# my.net
KiCad netlist of a schematic drawn in EAGLE
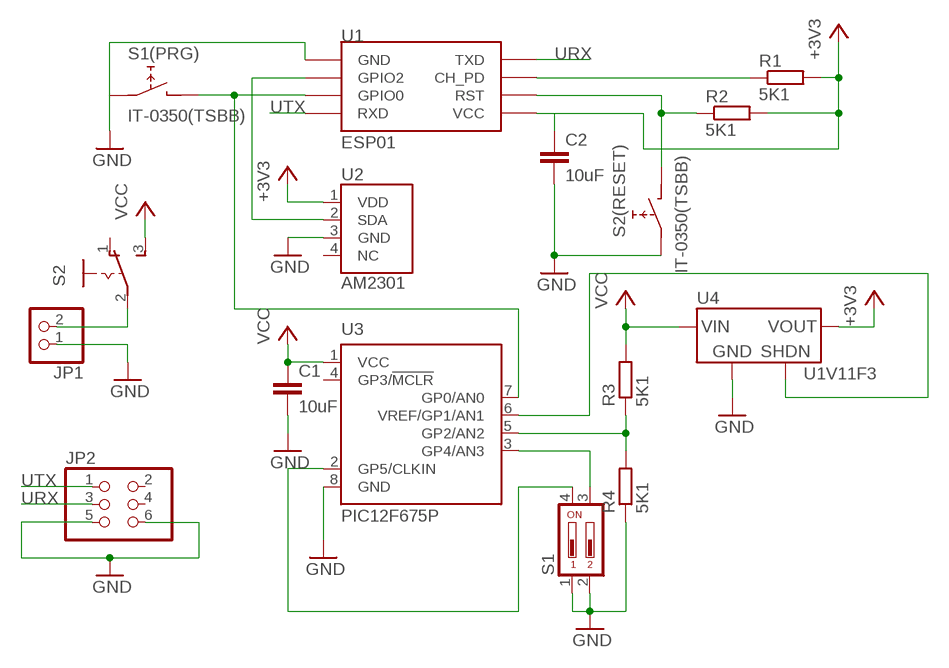
[diagram p0: schematic, sheet 1]

(export (version "E")
  (design (tool "Eeschema 10.0.6"))
  (components
    (comp (ref "C1")
      (value "10uF")
      (footprint "eagle-import:C3216")
      (libsource (lib "eagle-import") (part "C-EUC3216"))
    )
    (comp (ref "C2")
      (value "10uF")
      (footprint "eagle-import:C3216")
      (libsource (lib "eagle-import") (part "C-EUC3216"))
    )
    (comp (ref "JP1")
      (value "PINHD-1X2/90")
      (footprint "eagle-import:1X02_90")
      (libsource (lib "eagle-import") (part "PINHD-1X2/90"))
    )
    (comp (ref "JP2")
      (value "PINHD-2X3")
      (footprint "eagle-import:2X03")
      (libsource (lib "eagle-import") (part "PINHD-2X3"))
    )
    (comp (ref "R1")
      (value "5K1")
      (footprint "eagle-import:R3216")
      (libsource (lib "eagle-import") (part "R-EU_R3216"))
    )
    (comp (ref "R2")
      (value "5K1")
      (footprint "eagle-import:R3216")
      (libsource (lib "eagle-import") (part "R-EU_R3216"))
    )
    (comp (ref "R3")
      (value "5K1")
      (footprint "eagle-import:R3216")
      (libsource (lib "eagle-import") (part "R-EU_R3216"))
    )
    (comp (ref "R4")
      (value "5K1")
      (footprint "eagle-import:R3216")
      (libsource (lib "eagle-import") (part "R-EU_R3216"))
    )
    (comp (ref "S1")
      (value "DS02")
      (footprint "eagle-import:DS-02")
      (libsource (lib "eagle-import") (part "DS02"))
    )
    (comp (ref "S1(PRG)")
      (value "IT-0350(TSBB)")
      (footprint "eagle-import:TL1105L-4,3")
      (libsource (lib "eagle-import") (part "IT-0350(TSBB)"))
    )
    (comp (ref "S2")
      (value "SS-12D00")
      (footprint "eagle-import:M251")
      (libsource (lib "eagle-import") (part "SS-12D00"))
    )
    (comp (ref "S2(RESET)")
      (value "IT-0350(TSBB)")
      (footprint "eagle-import:TL1105L-4,3")
      (libsource (lib "eagle-import") (part "IT-0350(TSBB)"))
    )
    (comp (ref "U1")
      (value "ESP01")
      (footprint "eagle-import:ESP01")
      (libsource (lib "eagle-import") (part "ESP01"))
    )
    (comp (ref "U2")
      (value "AM2301")
      (footprint "eagle-import:AM2301-NO-COVER")
      (libsource (lib "eagle-import") (part "AM2301"))
    )
    (comp (ref "U3")
      (value "PIC12F675P")
      (footprint "eagle-import:DIL8")
      (fields (field (name "MF") "MICROCHIP") (field (name "MPN") "PIC12F675-E/P"))
      (libsource (lib "eagle-import") (part "PIC12F675P"))
    )
    (comp (ref "U4")
      (value "U1V11F3")
      (footprint "eagle-import:STEP-UP")
      (libsource (lib "eagle-import") (part "U1V11F3"))
    )
  )
  (nets
    (net (code "1") (name "+3V3") (class "Default")
      (node (ref "C2") (pin "1") (pinfunction "1_1") (pintype "passive"))
      (node (ref "R1") (pin "2") (pinfunction "2_2") (pintype "passive"))
      (node (ref "R2") (pin "2") (pinfunction "2_2") (pintype "passive"))
      (node (ref "U1") (pin "VCC") (pinfunction "VCC_VCC") (pintype "bidirectional"))
      (node (ref "U2") (pin "1") (pinfunction "VDD_1") (pintype "power_in"))
      (node (ref "U4") (pin "VOUT") (pinfunction "VOUT_VOUT") (pintype "output"))
    )
    (net (code "2") (name "/URX") (class "Default")
      (node (ref "JP2") (pin "3") (pinfunction "3_3") (pintype "passive"))
      (node (ref "U1") (pin "TX") (pinfunction "TXD_TX") (pintype "bidirectional"))
    )
    (net (code "3") (name "/UTX") (class "Default")
      (node (ref "JP2") (pin "1") (pinfunction "1_1") (pintype "passive"))
      (node (ref "U1") (pin "RX") (pinfunction "RXD_RX") (pintype "bidirectional"))
    )
    (net (code "4") (name "GND") (class "Default")
      (node (ref "C1") (pin "2") (pinfunction "2_2") (pintype "passive"))
      (node (ref "C2") (pin "2") (pinfunction "2_2") (pintype "passive"))
      (node (ref "JP1") (pin "1") (pinfunction "1_1") (pintype "passive"))
      (node (ref "JP2") (pin "5") (pinfunction "5_5") (pintype "passive"))
      (node (ref "JP2") (pin "6") (pinfunction "6_6") (pintype "passive"))
      (node (ref "R4") (pin "1") (pinfunction "1_1") (pintype "passive"))
      (node (ref "S1") (pin "1") (pinfunction "1_1") (pintype "passive"))
      (node (ref "S1") (pin "2") (pinfunction "2_2") (pintype "passive"))
      (node (ref "S1(PRG)") (pin "1") (pinfunction "1_1") (pintype "passive"))
      (node (ref "S2(RESET)") (pin "1") (pinfunction "1_1") (pintype "passive"))
      (node (ref "U1") (pin "GND") (pinfunction "GND_GND") (pintype "bidirectional"))
      (node (ref "U2") (pin "3") (pinfunction "GND_3") (pintype "power_in"))
      (node (ref "U3") (pin "8") (pinfunction "GND_8") (pintype "power_in"))
      (node (ref "U4") (pin "GND") (pinfunction "GND_GND") (pintype "power_in"))
    )
    (net (code "5") (name "Net-(R1-Pad1)") (class "Default")
      (node (ref "R1") (pin "1") (pinfunction "1_1") (pintype "passive"))
      (node (ref "U1") (pin "CH_PD") (pinfunction "CH_PD_CH_PD") (pintype "bidirectional"))
    )
    (net (code "6") (name "Net-(R2-Pad1)") (class "Default")
      (node (ref "R2") (pin "1") (pinfunction "1_1") (pintype "passive"))
      (node (ref "S2(RESET)") (pin "2") (pinfunction "2_2") (pintype "passive"))
      (node (ref "U1") (pin "RST") (pinfunction "RST_RST") (pintype "bidirectional"))
    )
    (net (code "7") (name "Net-(S2-P)") (class "Default")
      (node (ref "JP1") (pin "2") (pinfunction "2_2") (pintype "passive"))
      (node (ref "S2") (pin "2") (pinfunction "P_2") (pintype "passive"))
    )
    (net (code "8") (name "Net-(U2-SDA)") (class "Default")
      (node (ref "U1") (pin "GPIO2") (pinfunction "GPIO2_GPIO2") (pintype "bidirectional"))
      (node (ref "U2") (pin "2") (pinfunction "SDA_2") (pintype "bidirectional"))
    )
    (net (code "9") (name "Net-(U3-GP0{slash}AN0)") (class "Default")
      (node (ref "S1(PRG)") (pin "2") (pinfunction "2_2") (pintype "passive"))
      (node (ref "U1") (pin "GPIO0") (pinfunction "GPIO0_GPIO0") (pintype "bidirectional"))
      (node (ref "U3") (pin "7") (pinfunction "GP0/AN0_7") (pintype "bidirectional"))
    )
    (net (code "10") (name "Net-(U3-GP2{slash}AN2)") (class "Default")
      (node (ref "R3") (pin "1") (pinfunction "1_1") (pintype "passive"))
      (node (ref "R4") (pin "2") (pinfunction "2_2") (pintype "passive"))
      (node (ref "U3") (pin "5") (pinfunction "GP2/AN2_5") (pintype "bidirectional"))
    )
    (net (code "11") (name "Net-(U3-GP4{slash}AN3)") (class "Default")
      (node (ref "S1") (pin "3") (pinfunction "3_3") (pintype "passive"))
      (node (ref "U3") (pin "3") (pinfunction "GP4/AN3_3") (pintype "bidirectional"))
    )
    (net (code "12") (name "Net-(U3-GP5{slash}CLKIN)") (class "Default")
      (node (ref "S1") (pin "4") (pinfunction "4_4") (pintype "passive"))
      (node (ref "U3") (pin "2") (pinfunction "GP5/CLKIN_2") (pintype "bidirectional"))
    )
    (net (code "13") (name "Net-(U3-VREF{slash}GP1{slash}AN1)") (class "Default")
      (node (ref "U3") (pin "6") (pinfunction "VREF/GP1/AN1_6") (pintype "bidirectional"))
      (node (ref "U4") (pin "SHDN") (pinfunction "SHDN_SHDN") (pintype "input"))
    )
    (net (code "14") (name "VCC") (class "Default")
      (node (ref "C1") (pin "1") (pinfunction "1_1") (pintype "passive"))
      (node (ref "R3") (pin "2") (pinfunction "2_2") (pintype "passive"))
      (node (ref "S2") (pin "3") (pinfunction "S_3") (pintype "passive"))
      (node (ref "U3") (pin "1") (pinfunction "VCC_1") (pintype "power_in"))
      (node (ref "U4") (pin "VIN") (pinfunction "VIN_VIN") (pintype "input"))
    )
    (net (code "15") (name "unconnected-(JP2-Pad2)") (class "Default")
      (node (ref "JP2") (pin "2") (pinfunction "2_2") (pintype "passive"))
    )
    (net (code "16") (name "unconnected-(JP2-Pad4)") (class "Default")
      (node (ref "JP2") (pin "4") (pinfunction "4_4") (pintype "passive"))
    )
    (net (code "17") (name "unconnected-(S2-O-Pad1)") (class "Default")
      (node (ref "S2") (pin "1") (pinfunction "O_1") (pintype "passive"))
    )
    (net (code "18") (name "unconnected-(U2-NC-Pad4)") (class "Default")
      (node (ref "U2") (pin "4") (pinfunction "NC_4") (pintype "no_connect"))
    )
    (net (code "19") (name "unconnected-(U3-GP3{slash}~{MCLR}-Pad4)") (class "Default")
      (node (ref "U3") (pin "4") (pinfunction "GP3/~{MCLR}_4") (pintype "input"))
    )
  )
)
